# EEG_AFE_Sheet_3.net
KiCad netlist of a schematic drawn in Altium Designer
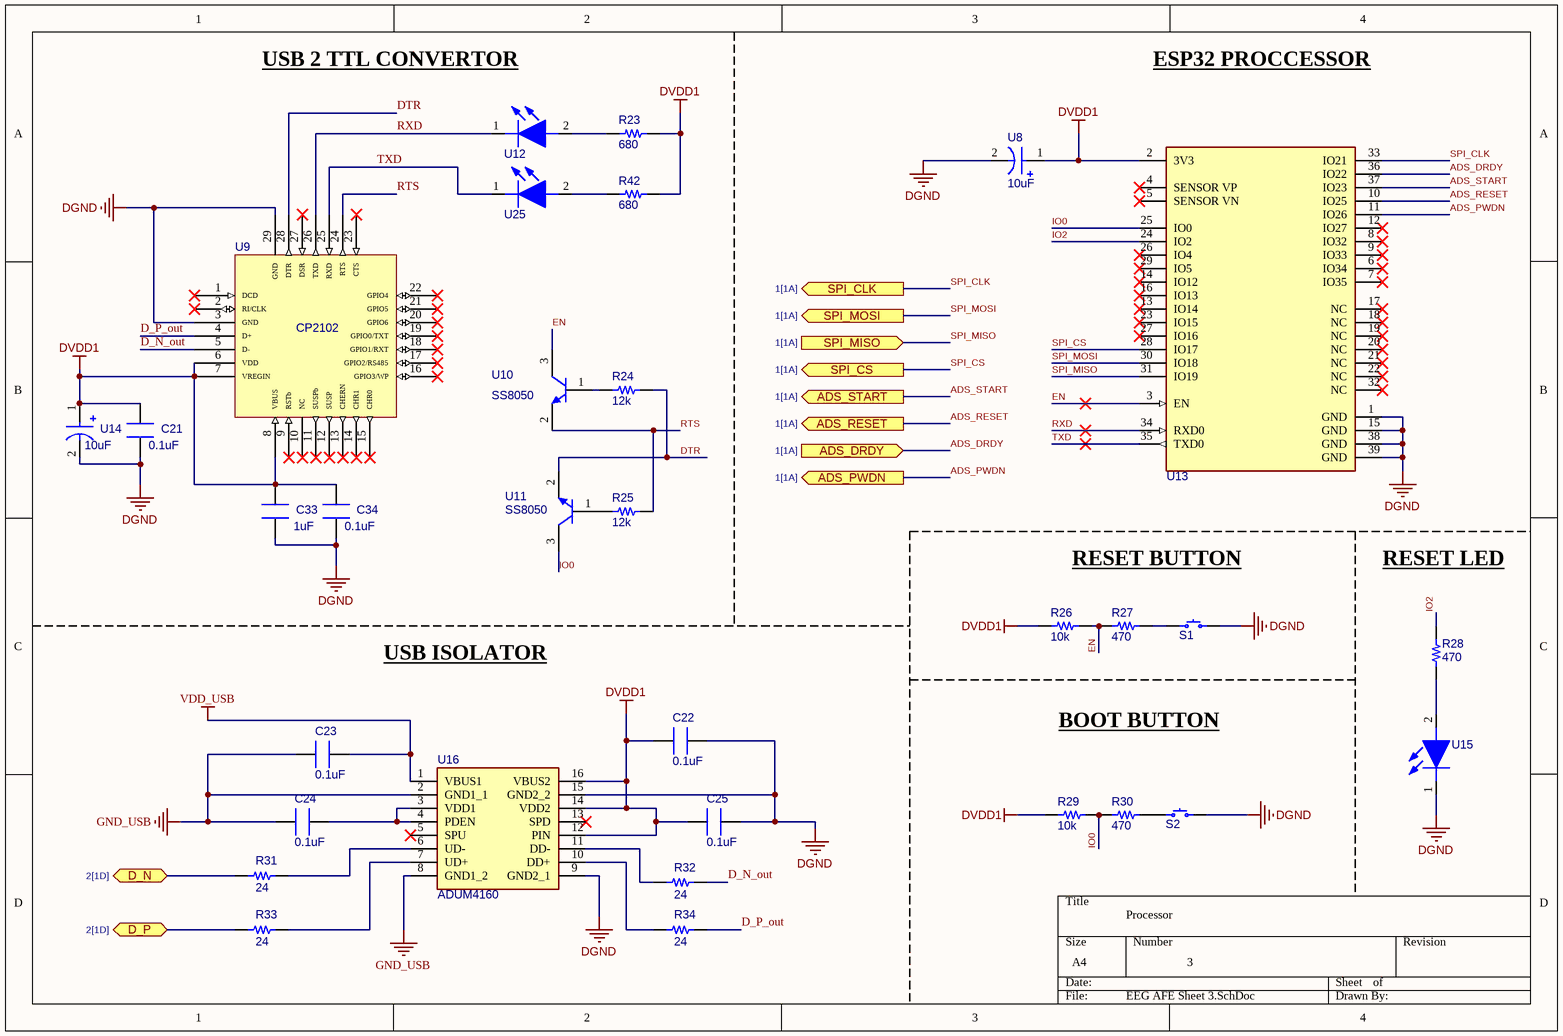
[diagram p0: EEG AFE Sheet 3.SchDoc]

(export (version "E")
  (design (tool "Eeschema 10.0.6"))
  (components
    (comp (ref "C21")
      (value "0.1uF")
      (footprint "CAP 0603_1608")
      (fields (field (name "MANUFACTURER") "???") (field (name "MANUFACTURER PART NUMBER") "08055C104KAT2A"))
      (libsource (lib "Schlib") (part "08055C104KAT2A"))
    )
    (comp (ref "C22")
      (value "0.1uF")
      (footprint "CAP 0603_1608")
      (fields (field (name "MANUFACTURER") "???") (field (name "MANUFACTURER PART NUMBER") "08055C104KAT2A"))
      (libsource (lib "Schlib") (part "08055C104KAT2A"))
    )
    (comp (ref "C23")
      (value "0.1uF")
      (footprint "CAP 0603_1608")
      (fields (field (name "MANUFACTURER") "???") (field (name "MANUFACTURER PART NUMBER") "08055C104KAT2A"))
      (libsource (lib "Schlib") (part "08055C104KAT2A"))
    )
    (comp (ref "C24")
      (value "0.1uF")
      (footprint "CAP 0603_1608")
      (fields (field (name "MANUFACTURER") "???") (field (name "MANUFACTURER PART NUMBER") "08055C104KAT2A"))
      (libsource (lib "Schlib") (part "08055C104KAT2A"))
    )
    (comp (ref "C25")
      (value "0.1uF")
      (footprint "CAP 0603_1608")
      (fields (field (name "MANUFACTURER") "???") (field (name "MANUFACTURER PART NUMBER") "08055C104KAT2A"))
      (libsource (lib "Schlib") (part "08055C104KAT2A"))
    )
    (comp (ref "C33")
      (value "1uF")
      (footprint "CAP 0603_1608")
      (fields (field (name "MANUFACTURER") "???") (field (name "MANUFACTURER PART NUMBER") "08055C104KAT2A"))
      (libsource (lib "Schlib") (part "08055C104KAT2A"))
    )
    (comp (ref "C34")
      (value "0.1uF")
      (footprint "CAP 0603_1608")
      (fields (field (name "MANUFACTURER") "???") (field (name "MANUFACTURER PART NUMBER") "08055C104KAT2A"))
      (libsource (lib "Schlib") (part "08055C104KAT2A"))
    )
    (comp (ref "R23")
      (value "680")
      (footprint "RES 0603_1608")
      (fields
        (field (name "MANUFACTURER") "???")
        (field (name "MANUFACTURER PART NUMBER") "RC0805FR-0710KL")
        (field (name "PUBLISHER") "Paraqum Technologies")
      )
      (libsource (lib "Schlib") (part "RC0805FR-0710KL"))
    )
    (comp (ref "R24")
      (value "12k")
      (footprint "RES 0603_1608")
      (fields
        (field (name "MANUFACTURER") "???")
        (field (name "MANUFACTURER PART NUMBER") "RC0805FR-0710KL")
        (field (name "PUBLISHER") "Paraqum Technologies")
      )
      (libsource (lib "Schlib") (part "RC0805FR-0710KL"))
    )
    (comp (ref "R25")
      (value "12k")
      (footprint "RES 0603_1608")
      (fields
        (field (name "MANUFACTURER") "???")
        (field (name "MANUFACTURER PART NUMBER") "RC0805FR-0710KL")
        (field (name "PUBLISHER") "Paraqum Technologies")
      )
      (libsource (lib "Schlib") (part "RC0805FR-0710KL"))
    )
    (comp (ref "R26")
      (value "10k")
      (footprint "RES 0603_1608")
      (fields
        (field (name "MANUFACTURER") "???")
        (field (name "MANUFACTURER PART NUMBER") "RC0805FR-0710KL")
        (field (name "PUBLISHER") "Paraqum Technologies")
      )
      (libsource (lib "Schlib") (part "RC0805FR-0710KL"))
    )
    (comp (ref "R27")
      (value "470")
      (footprint "RES 0603_1608")
      (fields
        (field (name "MANUFACTURER") "???")
        (field (name "MANUFACTURER PART NUMBER") "RC0805FR-0710KL")
        (field (name "PUBLISHER") "Paraqum Technologies")
      )
      (libsource (lib "Schlib") (part "RC0805FR-0710KL"))
    )
    (comp (ref "R28")
      (value "470")
      (footprint "RES 0603_1608")
      (fields
        (field (name "MANUFACTURER") "???")
        (field (name "MANUFACTURER PART NUMBER") "RC0805FR-0710KL")
        (field (name "PUBLISHER") "Paraqum Technologies")
      )
      (libsource (lib "Schlib") (part "RC0805FR-0710KL"))
    )
    (comp (ref "R29")
      (value "10k")
      (footprint "RES 0603_1608")
      (fields
        (field (name "MANUFACTURER") "???")
        (field (name "MANUFACTURER PART NUMBER") "RC0805FR-0710KL")
        (field (name "PUBLISHER") "Paraqum Technologies")
      )
      (libsource (lib "Schlib") (part "RC0805FR-0710KL"))
    )
    (comp (ref "R30")
      (value "470")
      (footprint "RES 0603_1608")
      (fields
        (field (name "MANUFACTURER") "???")
        (field (name "MANUFACTURER PART NUMBER") "RC0805FR-0710KL")
        (field (name "PUBLISHER") "Paraqum Technologies")
      )
      (libsource (lib "Schlib") (part "RC0805FR-0710KL"))
    )
    (comp (ref "R31")
      (value "24")
      (footprint "RES 0603_1608")
      (fields
        (field (name "MANUFACTURER") "???")
        (field (name "MANUFACTURER PART NUMBER") "RC0805FR-0710KL")
        (field (name "PUBLISHER") "Paraqum Technologies")
      )
      (libsource (lib "Schlib") (part "RC0805FR-0710KL"))
    )
    (comp (ref "R32")
      (value "24")
      (footprint "RES 0603_1608")
      (fields
        (field (name "MANUFACTURER") "???")
        (field (name "MANUFACTURER PART NUMBER") "RC0805FR-0710KL")
        (field (name "PUBLISHER") "Paraqum Technologies")
      )
      (libsource (lib "Schlib") (part "RC0805FR-0710KL"))
    )
    (comp (ref "R33")
      (value "24")
      (footprint "RES 0603_1608")
      (fields
        (field (name "MANUFACTURER") "???")
        (field (name "MANUFACTURER PART NUMBER") "RC0805FR-0710KL")
        (field (name "PUBLISHER") "Paraqum Technologies")
      )
      (libsource (lib "Schlib") (part "RC0805FR-0710KL"))
    )
    (comp (ref "R34")
      (value "24")
      (footprint "RES 0603_1608")
      (fields
        (field (name "MANUFACTURER") "???")
        (field (name "MANUFACTURER PART NUMBER") "RC0805FR-0710KL")
        (field (name "PUBLISHER") "Paraqum Technologies")
      )
      (libsource (lib "Schlib") (part "RC0805FR-0710KL"))
    )
    (comp (ref "R42")
      (value "680")
      (footprint "RES 0603_1608")
      (fields
        (field (name "MANUFACTURER") "???")
        (field (name "MANUFACTURER PART NUMBER") "RC0805FR-0710KL")
        (field (name "PUBLISHER") "Paraqum Technologies")
      )
      (libsource (lib "Schlib") (part "RC0805FR-0710KL"))
    )
    (comp (ref "S1")
      (value "*")
      (footprint "PTS636SM25FSMTRLFS")
      (fields
        (field (name "MANUFACTURER") "???")
        (field (name "MANUFACTURER PART NUMBER") "PTS636SM25FSMTRLFS")
        (field (name "PUBLISHER") "Paraqum Technologies")
      )
      (libsource (lib "Schlib") (part "PTS636SM25FSMTRLFS"))
    )
    (comp (ref "S2")
      (value "*")
      (footprint "PTS636SM25FSMTRLFS")
      (fields
        (field (name "MANUFACTURER") "???")
        (field (name "MANUFACTURER PART NUMBER") "PTS636SM25FSMTRLFS")
        (field (name "PUBLISHER") "Paraqum Technologies")
      )
      (libsource (lib "Schlib") (part "PTS636SM25FSMTRLFS"))
    )
    (comp (ref "U8")
      (value "10uF")
      (footprint "CAPC0805_TANT")
      (fields
        (field (name "MANUFACTURER") "???")
        (field (name "MANUFACTURER PART NUMBER") "TPSR105K025R4000")
        (field (name "PUBLISHER") "Paraqum Technologies")
      )
      (libsource (lib "Schlib") (part "TPSR105K025R4000"))
    )
    (comp (ref "U9")
      (value "CP2102")
      (footprint "QFN50P500X500X80_HS-29N")
      (description "USB Bus Controller, CMOS")
      (fields
        (field (name "MANUFACTURER") "???")
        (field (name "MANUFACTURER PART NUMBER") "CP2102N-A02-GQFN28R")
        (field (name "PUBLISHER") "Paraqum Technologies")
      )
      (libsource (lib "Schlib") (part "CP2102N-A02-GQFN28R"))
    )
    (comp (ref "U10")
      (value "SS8050")
      (footprint "MCCSEMI SOT-23-3")
      (description "Small Signal Bipolar Transistor, 1.5A I(C), 25V V(BR)CEO, 1-Element, NPN, Silicon")
      (fields
        (field (name "MANUFACTURER") "???")
        (field (name "MANUFACTURER PART NUMBER") "MMSS8050-H-TP")
        (field (name "PUBLISHER") "Paraqum Technologies")
      )
      (libsource (lib "Schlib") (part "MMSS8050-H-TP"))
    )
    (comp (ref "U11")
      (value "SS8050")
      (footprint "MCCSEMI SOT-23-3")
      (description "Small Signal Bipolar Transistor, 1.5A I(C), 25V V(BR)CEO, 1-Element, NPN, Silicon")
      (fields
        (field (name "MANUFACTURER") "???")
        (field (name "MANUFACTURER PART NUMBER") "MMSS8050-H-TP")
        (field (name "PUBLISHER") "Paraqum Technologies")
      )
      (libsource (lib "Schlib") (part "MMSS8050-H-TP"))
    )
    (comp (ref "U12")
      (value "*")
      (footprint "LEDC2012X80N")
      (description "Single Color LED, Blue, Water Clear, 1.4mm")
      (fields
        (field (name "MANUFACTURER") "???")
        (field (name "MANUFACTURER PART NUMBER") "150080BS75000")
        (field (name "PUBLISHER") "Paraqum Technologies")
      )
      (libsource (lib "Schlib") (part "150080BS75000"))
    )
    (comp (ref "U13")
      (value "*")
      (footprint "FP-ESP32-WROOM-32E_4MB-MFG")
      (description "Multiprotocol Modules SMD Module ESP32-WROOM-32E, ESP32-D0WD-V3, 4 MB SPI flash, PCB antenna")
      (fields
        (field (name "MANUFACTURER") "???")
        (field (name "MANUFACTURER PART NUMBER") "ESP32-WROOM-32E-N4")
        (field (name "PUBLISHER") "Paraqum Technologies")
      )
      (libsource (lib "Schlib") (part "ESP32-WROOM-32E-N4"))
    )
    (comp (ref "U14")
      (value "10uF")
      (footprint "CAPC0805_TANT")
      (fields
        (field (name "MANUFACTURER") "???")
        (field (name "MANUFACTURER PART NUMBER") "TPSR105K025R4000")
        (field (name "PUBLISHER") "Paraqum Technologies")
      )
      (libsource (lib "Schlib") (part "TPSR105K025R4000"))
    )
    (comp (ref "U15")
      (value "*")
      (footprint "LEDC2012X80N")
      (description "Single Color LED, Blue, Water Clear, 1.4mm")
      (fields
        (field (name "MANUFACTURER") "???")
        (field (name "MANUFACTURER PART NUMBER") "150080BS75000")
        (field (name "PUBLISHER") "Paraqum Technologies")
      )
      (libsource (lib "Schlib") (part "150080BS75000"))
    )
    (comp (ref "U16")
      (value "ADUM4160")
      (footprint "SOIC127P1030X265-16N")
      (description "Interface Circuit, CMOS, PDSO16")
      (fields
        (field (name "MANUFACTURER") "???")
        (field (name "MANUFACTURER PART NUMBER") "ADUM4160BRWZ")
        (field (name "PUBLISHER") "Paraqum Technologies")
      )
      (libsource (lib "Schlib") (part "ADUM4160BRWZ"))
    )
    (comp (ref "U25")
      (value "*")
      (footprint "LEDC2012X80N")
      (description "Single Color LED, Blue, Water Clear, 1.4mm")
      (fields
        (field (name "MANUFACTURER") "???")
        (field (name "MANUFACTURER PART NUMBER") "150080BS75000")
        (field (name "PUBLISHER") "Paraqum Technologies")
      )
      (libsource (lib "Schlib") (part "150080BS75000"))
    )
  )
  (nets
    (net (code "1") (name "/ADS_DRDY") (class "Default")
      (node (ref "U13") (pin "36") (pinfunction "IO22_36") (pintype "passive"))
    )
    (net (code "2") (name "/ADS_PWDN") (class "Default")
      (node (ref "U13") (pin "11") (pinfunction "IO26_11") (pintype "passive"))
    )
    (net (code "3") (name "/ADS_RESET") (class "Default")
      (node (ref "U13") (pin "10") (pinfunction "IO25_10") (pintype "passive"))
    )
    (net (code "4") (name "/ADS_START") (class "Default")
      (node (ref "U13") (pin "37") (pinfunction "IO23_37") (pintype "passive"))
    )
    (net (code "5") (name "/DTR") (class "Default")
      (node (ref "R24") (pin "1") (pinfunction "1_1") (pintype "passive"))
      (node (ref "U11") (pin "2") (pinfunction "E_2") (pintype "passive"))
      (node (ref "U9") (pin "28") (pinfunction "DTR_28") (pintype "output"))
    )
    (net (code "6") (name "/D_N") (class "Default")
      (node (ref "R31") (pin "2") (pinfunction "2_2") (pintype "passive"))
    )
    (net (code "7") (name "/D_N_out") (class "Default")
      (node (ref "R32") (pin "1") (pinfunction "1_1") (pintype "passive"))
      (node (ref "U9") (pin "5") (pinfunction "D-_5") (pintype "passive"))
    )
    (net (code "8") (name "/D_P") (class "Default")
      (node (ref "R33") (pin "2") (pinfunction "2_2") (pintype "passive"))
    )
    (net (code "9") (name "/D_P_out") (class "Default")
      (node (ref "R34") (pin "1") (pinfunction "1_1") (pintype "passive"))
      (node (ref "U9") (pin "4") (pinfunction "D+_4") (pintype "passive"))
    )
    (net (code "10") (name "/EN") (class "Default")
      (node (ref "R26") (pin "2") (pinfunction "2_2") (pintype "passive"))
      (node (ref "R27") (pin "1") (pinfunction "1_1") (pintype "passive"))
      (node (ref "U10") (pin "3") (pinfunction "C_3") (pintype "passive"))
      (node (ref "U13") (pin "3") (pinfunction "EN_3") (pintype "input"))
    )
    (net (code "11") (name "/IO0") (class "Default")
      (node (ref "R29") (pin "2") (pinfunction "2_2") (pintype "passive"))
      (node (ref "R30") (pin "1") (pinfunction "1_1") (pintype "passive"))
      (node (ref "U11") (pin "3") (pinfunction "C_3") (pintype "passive"))
      (node (ref "U13") (pin "25") (pinfunction "IO0_25") (pintype "passive"))
    )
    (net (code "12") (name "/IO2") (class "Default")
      (node (ref "R28") (pin "2") (pinfunction "2_2") (pintype "passive"))
      (node (ref "U13") (pin "24") (pinfunction "IO2_24") (pintype "passive"))
    )
    (net (code "13") (name "/RTS") (class "Default")
      (node (ref "R25") (pin "1") (pinfunction "1_1") (pintype "passive"))
      (node (ref "U10") (pin "2") (pinfunction "E_2") (pintype "passive"))
      (node (ref "U9") (pin "24") (pinfunction "RTS_24") (pintype "output"))
    )
    (net (code "14") (name "/RXD") (class "Default")
      (node (ref "U12") (pin "1") (pinfunction "K_1") (pintype "passive"))
      (node (ref "U13") (pin "34") (pinfunction "RXD0_34") (pintype "input"))
      (node (ref "U9") (pin "26") (pinfunction "TXD_26") (pintype "output"))
    )
    (net (code "15") (name "/SPI_CLK") (class "Default")
      (node (ref "U13") (pin "33") (pinfunction "IO21_33") (pintype "passive"))
    )
    (net (code "16") (name "/SPI_CS") (class "Default")
      (node (ref "U13") (pin "28") (pinfunction "IO17_28") (pintype "passive"))
    )
    (net (code "17") (name "/SPI_MISO") (class "Default")
      (node (ref "U13") (pin "31") (pinfunction "IO19_31") (pintype "passive"))
    )
    (net (code "18") (name "/SPI_MOSI") (class "Default")
      (node (ref "U13") (pin "30") (pinfunction "IO18_30") (pintype "passive"))
    )
    (net (code "19") (name "/TXD") (class "Default")
      (node (ref "U13") (pin "35") (pinfunction "TXD0_35") (pintype "output"))
      (node (ref "U25") (pin "1") (pinfunction "K_1") (pintype "passive"))
      (node (ref "U9") (pin "25") (pinfunction "RXD_25") (pintype "input"))
    )
    (net (code "20") (name "DGND") (class "Default")
      (node (ref "C21") (pin "1") (pinfunction "1_1") (pintype "passive"))
      (node (ref "C22") (pin "1") (pinfunction "1_1") (pintype "passive"))
      (node (ref "C25") (pin "1") (pinfunction "1_1") (pintype "passive"))
      (node (ref "C33") (pin "1") (pinfunction "1_1") (pintype "passive"))
      (node (ref "C34") (pin "1") (pinfunction "1_1") (pintype "passive"))
      (node (ref "S1") (pin "1") (pinfunction "1_1") (pintype "passive"))
      (node (ref "S2") (pin "1") (pinfunction "1_1") (pintype "passive"))
      (node (ref "U13") (pin "1") (pinfunction "GND_1") (pintype "power_in"))
      (node (ref "U13") (pin "15") (pinfunction "GND_15") (pintype "power_in"))
      (node (ref "U13") (pin "38") (pinfunction "GND_38") (pintype "power_in"))
      (node (ref "U13") (pin "39") (pinfunction "GND_39") (pintype "power_in"))
      (node (ref "U14") (pin "2") (pinfunction "A_2") (pintype "passive"))
      (node (ref "U15") (pin "1") (pinfunction "K_1") (pintype "passive"))
      (node (ref "U16") (pin "15") (pinfunction "GND2_2_15") (pintype "passive"))
      (node (ref "U16") (pin "9") (pinfunction "GND2_1_9") (pintype "passive"))
      (node (ref "U8") (pin "2") (pinfunction "A_2") (pintype "passive"))
      (node (ref "U9") (pin "29") (pinfunction "GND_29") (pintype "power_in"))
      (node (ref "U9") (pin "3") (pinfunction "GND_3") (pintype "power_in"))
    )
    (net (code "21") (name "DVDD1") (class "Default")
      (node (ref "C21") (pin "2") (pinfunction "2_2") (pintype "passive"))
      (node (ref "C22") (pin "2") (pinfunction "2_2") (pintype "passive"))
      (node (ref "C25") (pin "2") (pinfunction "2_2") (pintype "passive"))
      (node (ref "C33") (pin "2") (pinfunction "2_2") (pintype "passive"))
      (node (ref "C34") (pin "2") (pinfunction "2_2") (pintype "passive"))
      (node (ref "R23") (pin "1") (pinfunction "1_1") (pintype "passive"))
      (node (ref "R26") (pin "1") (pinfunction "1_1") (pintype "passive"))
      (node (ref "R29") (pin "1") (pinfunction "1_1") (pintype "passive"))
      (node (ref "R42") (pin "1") (pinfunction "1_1") (pintype "passive"))
      (node (ref "U13") (pin "2") (pinfunction "3V3_2") (pintype "power_in"))
      (node (ref "U14") (pin "1") (pinfunction "C_1") (pintype "passive"))
      (node (ref "U16") (pin "12") (pinfunction "PIN_12") (pintype "passive"))
      (node (ref "U16") (pin "14") (pinfunction "VDD2_14") (pintype "passive"))
      (node (ref "U16") (pin "16") (pinfunction "VBUS2_16") (pintype "passive"))
      (node (ref "U8") (pin "1") (pinfunction "C_1") (pintype "passive"))
      (node (ref "U9") (pin "6") (pinfunction "VDD_6") (pintype "power_in"))
      (node (ref "U9") (pin "7") (pinfunction "VREGIN_7") (pintype "passive"))
      (node (ref "U9") (pin "8") (pinfunction "VBUS_8") (pintype "input"))
    )
    (net (code "22") (name "GND_USB") (class "Default")
      (node (ref "C23") (pin "2") (pinfunction "2_2") (pintype "passive"))
      (node (ref "C24") (pin "2") (pinfunction "2_2") (pintype "passive"))
      (node (ref "U16") (pin "2") (pinfunction "GND1_1_2") (pintype "passive"))
      (node (ref "U16") (pin "8") (pinfunction "GND1_2_8") (pintype "passive"))
    )
    (net (code "23") (name "Net-(R27-Pad2)") (class "Default")
      (node (ref "R27") (pin "2") (pinfunction "2_2") (pintype "passive"))
      (node (ref "S1") (pin "2") (pinfunction "2_2") (pintype "passive"))
    )
    (net (code "24") (name "Net-(R30-Pad2)") (class "Default")
      (node (ref "R30") (pin "2") (pinfunction "2_2") (pintype "passive"))
      (node (ref "S2") (pin "2") (pinfunction "2_2") (pintype "passive"))
    )
    (net (code "25") (name "Net-(U10-B)") (class "Default")
      (node (ref "R24") (pin "2") (pinfunction "2_2") (pintype "passive"))
      (node (ref "U10") (pin "1") (pinfunction "B_1") (pintype "passive"))
    )
    (net (code "26") (name "Net-(U11-B)") (class "Default")
      (node (ref "R25") (pin "2") (pinfunction "2_2") (pintype "passive"))
      (node (ref "U11") (pin "1") (pinfunction "B_1") (pintype "passive"))
    )
    (net (code "27") (name "Net-(U12-A)") (class "Default")
      (node (ref "R23") (pin "2") (pinfunction "2_2") (pintype "passive"))
      (node (ref "U12") (pin "2") (pinfunction "A_2") (pintype "passive"))
    )
    (net (code "28") (name "Net-(U15-A)") (class "Default")
      (node (ref "R28") (pin "1") (pinfunction "1_1") (pintype "passive"))
      (node (ref "U15") (pin "2") (pinfunction "A_2") (pintype "passive"))
    )
    (net (code "29") (name "Net-(U16-DD+)") (class "Default")
      (node (ref "R34") (pin "2") (pinfunction "2_2") (pintype "passive"))
      (node (ref "U16") (pin "10") (pinfunction "DD+_10") (pintype "passive"))
    )
    (net (code "30") (name "Net-(U16-DD-)") (class "Default")
      (node (ref "R32") (pin "2") (pinfunction "2_2") (pintype "passive"))
      (node (ref "U16") (pin "11") (pinfunction "DD-_11") (pintype "passive"))
    )
    (net (code "31") (name "Net-(U16-PDEN)") (class "Default")
      (node (ref "C24") (pin "1") (pinfunction "1_1") (pintype "passive"))
      (node (ref "U16") (pin "3") (pinfunction "VDD1_3") (pintype "passive"))
      (node (ref "U16") (pin "4") (pinfunction "PDEN_4") (pintype "passive"))
    )
    (net (code "32") (name "Net-(U16-UD+)") (class "Default")
      (node (ref "R33") (pin "1") (pinfunction "1_1") (pintype "passive"))
      (node (ref "U16") (pin "7") (pinfunction "UD+_7") (pintype "passive"))
    )
    (net (code "33") (name "Net-(U16-UD-)") (class "Default")
      (node (ref "R31") (pin "1") (pinfunction "1_1") (pintype "passive"))
      (node (ref "U16") (pin "6") (pinfunction "UD-_6") (pintype "passive"))
    )
    (net (code "34") (name "Net-(U25-A)") (class "Default")
      (node (ref "R42") (pin "2") (pinfunction "2_2") (pintype "passive"))
      (node (ref "U25") (pin "2") (pinfunction "A_2") (pintype "passive"))
    )
    (net (code "35") (name "VDD_USB") (class "Default")
      (node (ref "C23") (pin "1") (pinfunction "1_1") (pintype "passive"))
      (node (ref "U16") (pin "1") (pinfunction "VBUS1_1") (pintype "passive"))
    )
    (net (code "36") (name "unconnected-(U9-CHERN-Pad13)") (class "Default")
      (node (ref "U9") (pin "13") (pinfunction "CHERN_13") (pintype "output+no_connect"))
    )
    (net (code "37") (name "unconnected-(U9-CHR0-Pad15)") (class "Default")
      (node (ref "U9") (pin "15") (pinfunction "CHR0_15") (pintype "output+no_connect"))
    )
    (net (code "38") (name "unconnected-(U9-CHR1-Pad14)") (class "Default")
      (node (ref "U9") (pin "14") (pinfunction "CHR1_14") (pintype "output+no_connect"))
    )
    (net (code "39") (name "unconnected-(U9-CTS-Pad23)") (class "Default")
      (node (ref "U9") (pin "23") (pinfunction "CTS_23") (pintype "input+no_connect"))
    )
    (net (code "40") (name "unconnected-(U9-DCD-Pad1)") (class "Default")
      (node (ref "U9") (pin "1") (pinfunction "DCD_1") (pintype "input+no_connect"))
    )
    (net (code "41") (name "unconnected-(U9-DSR-Pad27)") (class "Default")
      (node (ref "U9") (pin "27") (pinfunction "DSR_27") (pintype "input+no_connect"))
    )
    (net (code "42") (name "unconnected-(U9-GPIO0{slash}TXT-Pad19)") (class "Default")
      (node (ref "U9") (pin "19") (pinfunction "GPIO0/TXT_19") (pintype "bidirectional+no_connect"))
    )
    (net (code "43") (name "unconnected-(U9-GPIO1{slash}RXT-Pad18)") (class "Default")
      (node (ref "U9") (pin "18") (pinfunction "GPIO1/RXT_18") (pintype "bidirectional+no_connect"))
    )
    (net (code "44") (name "unconnected-(U9-GPIO2{slash}RS485-Pad17)") (class "Default")
      (node (ref "U9") (pin "17") (pinfunction "GPIO2/RS485_17") (pintype "bidirectional+no_connect"))
    )
    (net (code "45") (name "unconnected-(U9-GPIO3{slash}WP-Pad16)") (class "Default")
      (node (ref "U9") (pin "16") (pinfunction "GPIO3/WP_16") (pintype "bidirectional+no_connect"))
    )
    (net (code "46") (name "unconnected-(U9-GPIO4-Pad22)") (class "Default")
      (node (ref "U9") (pin "22") (pinfunction "GPIO4_22") (pintype "bidirectional+no_connect"))
    )
    (net (code "47") (name "unconnected-(U9-GPIO5-Pad21)") (class "Default")
      (node (ref "U9") (pin "21") (pinfunction "GPIO5_21") (pintype "bidirectional+no_connect"))
    )
    (net (code "48") (name "unconnected-(U9-GPIO6-Pad20)") (class "Default")
      (node (ref "U9") (pin "20") (pinfunction "GPIO6_20") (pintype "bidirectional+no_connect"))
    )
    (net (code "49") (name "unconnected-(U9-NC-Pad10)") (class "Default")
      (node (ref "U9") (pin "10") (pinfunction "NC_10") (pintype "tri_state+no_connect"))
    )
    (net (code "50") (name "unconnected-(U9-RI{slash}CLK-Pad2)") (class "Default")
      (node (ref "U9") (pin "2") (pinfunction "RI/CLK_2") (pintype "bidirectional+no_connect"))
    )
    (net (code "51") (name "unconnected-(U9-RSTb-Pad9)") (class "Default")
      (node (ref "U9") (pin "9") (pinfunction "RSTb_9") (pintype "input+no_connect"))
    )
    (net (code "52") (name "unconnected-(U9-SUSP-Pad12)") (class "Default")
      (node (ref "U9") (pin "12") (pinfunction "SUSP_12") (pintype "output+no_connect"))
    )
    (net (code "53") (name "unconnected-(U9-SUSPb-Pad11)") (class "Default")
      (node (ref "U9") (pin "11") (pinfunction "SUSPb_11") (pintype "output+no_connect"))
    )
    (net (code "54") (name "unconnected-(U13-IO4-Pad26)") (class "Default")
      (node (ref "U13") (pin "26") (pinfunction "IO4_26") (pintype "passive+no_connect"))
    )
    (net (code "55") (name "unconnected-(U13-IO5-Pad29)") (class "Default")
      (node (ref "U13") (pin "29") (pinfunction "IO5_29") (pintype "passive+no_connect"))
    )
    (net (code "56") (name "unconnected-(U13-IO12-Pad14)") (class "Default")
      (node (ref "U13") (pin "14") (pinfunction "IO12_14") (pintype "passive+no_connect"))
    )
    (net (code "57") (name "unconnected-(U13-IO13-Pad16)") (class "Default")
      (node (ref "U13") (pin "16") (pinfunction "IO13_16") (pintype "passive+no_connect"))
    )
    (net (code "58") (name "unconnected-(U13-IO14-Pad13)") (class "Default")
      (node (ref "U13") (pin "13") (pinfunction "IO14_13") (pintype "passive+no_connect"))
    )
    (net (code "59") (name "unconnected-(U13-IO15-Pad23)") (class "Default")
      (node (ref "U13") (pin "23") (pinfunction "IO15_23") (pintype "passive+no_connect"))
    )
    (net (code "60") (name "unconnected-(U13-IO16-Pad27)") (class "Default")
      (node (ref "U13") (pin "27") (pinfunction "IO16_27") (pintype "passive+no_connect"))
    )
    (net (code "61") (name "unconnected-(U13-IO27-Pad12)") (class "Default")
      (node (ref "U13") (pin "12") (pinfunction "IO27_12") (pintype "passive+no_connect"))
    )
    (net (code "62") (name "unconnected-(U13-IO32-Pad8)") (class "Default")
      (node (ref "U13") (pin "8") (pinfunction "IO32_8") (pintype "passive+no_connect"))
    )
    (net (code "63") (name "unconnected-(U13-IO33-Pad9)") (class "Default")
      (node (ref "U13") (pin "9") (pinfunction "IO33_9") (pintype "passive+no_connect"))
    )
    (net (code "64") (name "unconnected-(U13-IO34-Pad6)") (class "Default")
      (node (ref "U13") (pin "6") (pinfunction "IO34_6") (pintype "passive+no_connect"))
    )
    (net (code "65") (name "unconnected-(U13-IO35-Pad7)") (class "Default")
      (node (ref "U13") (pin "7") (pinfunction "IO35_7") (pintype "passive+no_connect"))
    )
    (net (code "66") (name "unconnected-(U13-NC-Pad17)") (class "Default")
      (node (ref "U13") (pin "17") (pinfunction "NC_17") (pintype "passive+no_connect"))
    )
    (net (code "67") (name "unconnected-(U13-NC-Pad18)") (class "Default")
      (node (ref "U13") (pin "18") (pinfunction "NC_18") (pintype "passive+no_connect"))
    )
    (net (code "68") (name "unconnected-(U13-NC-Pad19)") (class "Default")
      (node (ref "U13") (pin "19") (pinfunction "NC_19") (pintype "passive+no_connect"))
    )
    (net (code "69") (name "unconnected-(U13-NC-Pad20)") (class "Default")
      (node (ref "U13") (pin "20") (pinfunction "NC_20") (pintype "passive+no_connect"))
    )
    (net (code "70") (name "unconnected-(U13-NC-Pad21)") (class "Default")
      (node (ref "U13") (pin "21") (pinfunction "NC_21") (pintype "passive+no_connect"))
    )
    (net (code "71") (name "unconnected-(U13-NC-Pad22)") (class "Default")
      (node (ref "U13") (pin "22") (pinfunction "NC_22") (pintype "passive+no_connect"))
    )
    (net (code "72") (name "unconnected-(U13-NC-Pad32)") (class "Default")
      (node (ref "U13") (pin "32") (pinfunction "NC_32") (pintype "passive+no_connect"))
    )
    (net (code "73") (name "unconnected-(U13-SENSOR_VN-Pad5)") (class "Default")
      (node (ref "U13") (pin "5") (pinfunction "SENSOR_VN_5") (pintype "passive+no_connect"))
    )
    (net (code "74") (name "unconnected-(U13-SENSOR_VP-Pad4)") (class "Default")
      (node (ref "U13") (pin "4") (pinfunction "SENSOR_VP_4") (pintype "passive+no_connect"))
    )
    (net (code "75") (name "unconnected-(U16-SPD-Pad13)") (class "Default")
      (node (ref "U16") (pin "13") (pinfunction "SPD_13") (pintype "passive+no_connect"))
    )
    (net (code "76") (name "unconnected-(U16-SPU-Pad5)") (class "Default")
      (node (ref "U16") (pin "5") (pinfunction "SPU_5") (pintype "passive+no_connect"))
    )
  )
)
